# Pure_Sequencer.net
KiCad netlist of a schematic drawn in EAGLE
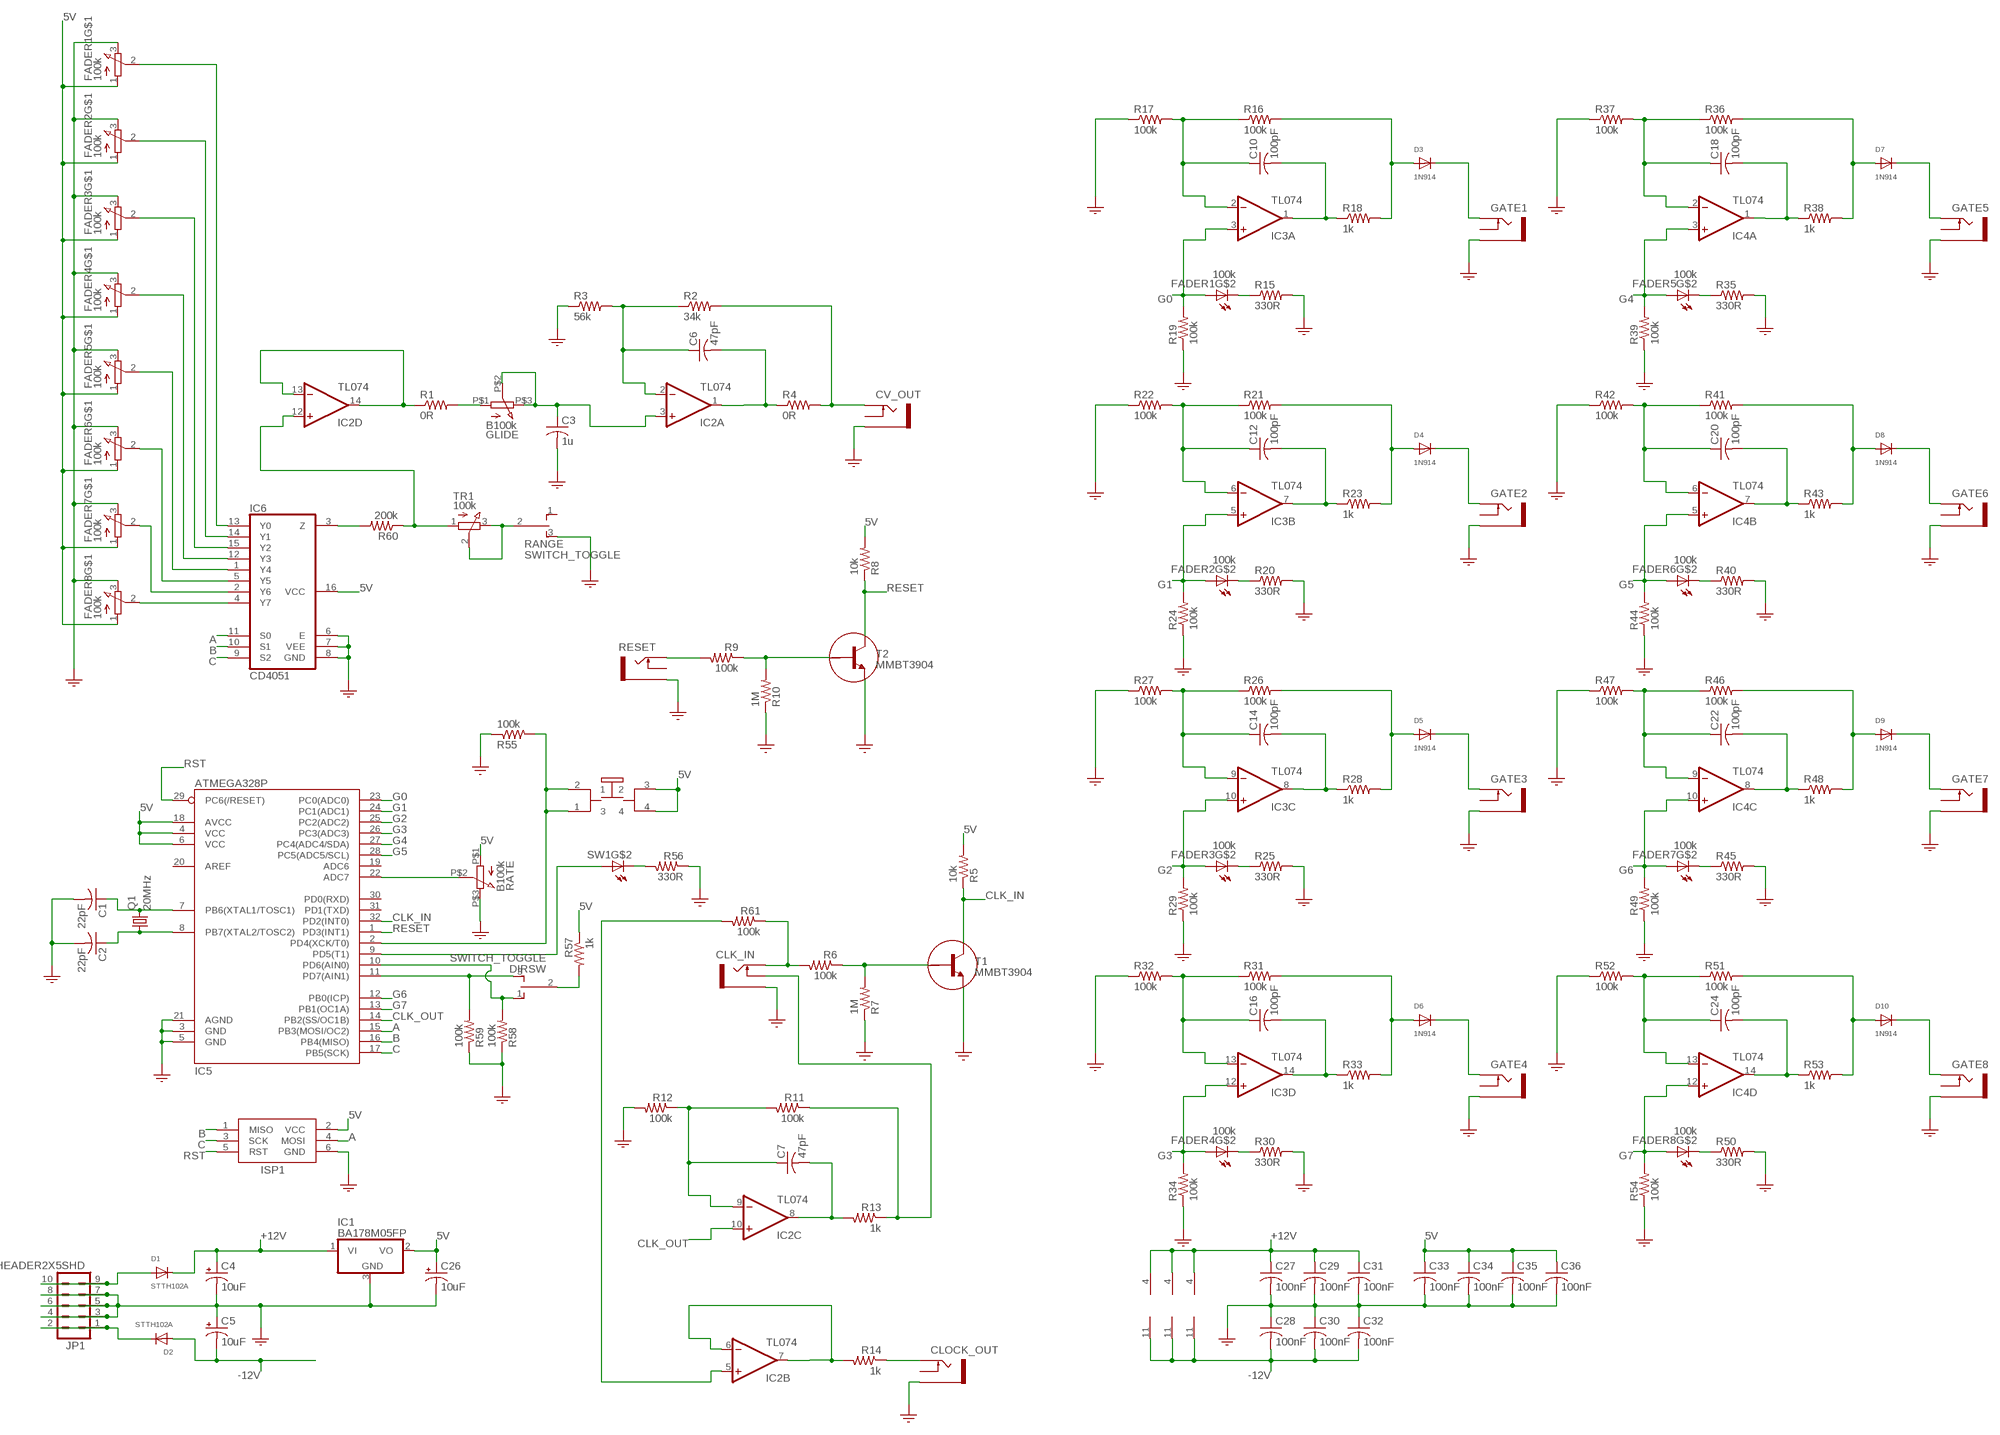
[diagram p0: schematic, sheet 1]

(export (version "E")
  (design (tool "Eeschema 10.0.6"))
  (components
    (comp (ref "C1")
      (value "22pF")
      (footprint "eagle-import:C0805")
      (libsource (lib "eagle-import") (part "CAPACITOR-USC0805"))
    )
    (comp (ref "C2")
      (value "22pF")
      (footprint "eagle-import:C0805")
      (libsource (lib "eagle-import") (part "CAPACITOR-USC0805"))
    )
    (comp (ref "C3")
      (value "1u")
      (footprint "eagle-import:C0805")
      (libsource (lib "eagle-import") (part "CAPACITOR-USC0805"))
    )
    (comp (ref "C4")
      (value "10uF")
      (footprint "eagle-import:153CLV-0505")
      (libsource (lib "eagle-import") (part "CAPACITOR_POL-US153CLV-0505"))
    )
    (comp (ref "C5")
      (value "10uF")
      (footprint "eagle-import:153CLV-0505")
      (libsource (lib "eagle-import") (part "CAPACITOR_POL-US153CLV-0505"))
    )
    (comp (ref "C6")
      (value "47pF")
      (footprint "eagle-import:C0805")
      (libsource (lib "eagle-import") (part "CAPACITOR-USC0805"))
    )
    (comp (ref "C7")
      (value "47pF")
      (footprint "eagle-import:C0805")
      (libsource (lib "eagle-import") (part "CAPACITOR-USC0805"))
    )
    (comp (ref "C10")
      (value "100pF")
      (footprint "eagle-import:C0805")
      (libsource (lib "eagle-import") (part "CAPACITOR-USC0805"))
    )
    (comp (ref "C12")
      (value "100pF")
      (footprint "eagle-import:C0805")
      (libsource (lib "eagle-import") (part "CAPACITOR-USC0805"))
    )
    (comp (ref "C14")
      (value "100pF")
      (footprint "eagle-import:C0805")
      (libsource (lib "eagle-import") (part "CAPACITOR-USC0805"))
    )
    (comp (ref "C16")
      (value "100pF")
      (footprint "eagle-import:C0805")
      (libsource (lib "eagle-import") (part "CAPACITOR-USC0805"))
    )
    (comp (ref "C18")
      (value "100pF")
      (footprint "eagle-import:C0805")
      (libsource (lib "eagle-import") (part "CAPACITOR-USC0805"))
    )
    (comp (ref "C20")
      (value "100pF")
      (footprint "eagle-import:C0805")
      (libsource (lib "eagle-import") (part "CAPACITOR-USC0805"))
    )
    (comp (ref "C22")
      (value "100pF")
      (footprint "eagle-import:C0805")
      (libsource (lib "eagle-import") (part "CAPACITOR-USC0805"))
    )
    (comp (ref "C24")
      (value "100pF")
      (footprint "eagle-import:C0805")
      (libsource (lib "eagle-import") (part "CAPACITOR-USC0805"))
    )
    (comp (ref "C26")
      (value "10uF")
      (footprint "eagle-import:153CLV-0505")
      (libsource (lib "eagle-import") (part "CAPACITOR_POL-US153CLV-0505"))
    )
    (comp (ref "C27")
      (value "100nF")
      (footprint "eagle-import:C0805")
      (libsource (lib "eagle-import") (part "CAPACITOR-USC0805"))
    )
    (comp (ref "C28")
      (value "100nF")
      (footprint "eagle-import:C0805")
      (libsource (lib "eagle-import") (part "CAPACITOR-USC0805"))
    )
    (comp (ref "C29")
      (value "100nF")
      (footprint "eagle-import:C0805")
      (libsource (lib "eagle-import") (part "CAPACITOR-USC0805"))
    )
    (comp (ref "C30")
      (value "100nF")
      (footprint "eagle-import:C0805")
      (libsource (lib "eagle-import") (part "CAPACITOR-USC0805"))
    )
    (comp (ref "C31")
      (value "100nF")
      (footprint "eagle-import:C0805")
      (libsource (lib "eagle-import") (part "CAPACITOR-USC0805"))
    )
    (comp (ref "C32")
      (value "100nF")
      (footprint "eagle-import:C0805")
      (libsource (lib "eagle-import") (part "CAPACITOR-USC0805"))
    )
    (comp (ref "C33")
      (value "100nF")
      (footprint "eagle-import:C0805")
      (libsource (lib "eagle-import") (part "CAPACITOR-USC0805"))
    )
    (comp (ref "C34")
      (value "100nF")
      (footprint "eagle-import:C0805")
      (libsource (lib "eagle-import") (part "CAPACITOR-USC0805"))
    )
    (comp (ref "C35")
      (value "100nF")
      (footprint "eagle-import:C0805")
      (libsource (lib "eagle-import") (part "CAPACITOR-USC0805"))
    )
    (comp (ref "C36")
      (value "100nF")
      (footprint "eagle-import:C0805")
      (libsource (lib "eagle-import") (part "CAPACITOR-USC0805"))
    )
    (comp (ref "CLK_IN")
      (value "PJ301M-12")
      (footprint "eagle-import:PJ301M-12")
      (libsource (lib "eagle-import") (part "SOCKET_MONO_3.5MMPJ301M-12"))
    )
    (comp (ref "CLOCK_OUT")
      (value "PJ301M-12")
      (footprint "eagle-import:PJ301M-12")
      (libsource (lib "eagle-import") (part "SOCKET_MONO_3.5MMPJ301M-12"))
    )
    (comp (ref "CV_OUT")
      (value "PJ301M-12")
      (footprint "eagle-import:PJ301M-12")
      (libsource (lib "eagle-import") (part "SOCKET_MONO_3.5MMPJ301M-12"))
    )
    (comp (ref "D1")
      (value "STTH102A")
      (footprint "eagle-import:SMADIODE")
      (libsource (lib "eagle-import") (part "DIODESMA"))
    )
    (comp (ref "D2")
      (value "STTH102A")
      (footprint "eagle-import:SMADIODE")
      (libsource (lib "eagle-import") (part "DIODESMA"))
    )
    (comp (ref "D3")
      (value "1N914")
      (footprint "eagle-import:DO-41")
      (libsource (lib "eagle-import") (part "DIODEDO-41"))
    )
    (comp (ref "D4")
      (value "1N914")
      (footprint "eagle-import:DO-41")
      (libsource (lib "eagle-import") (part "DIODEDO-41"))
    )
    (comp (ref "D5")
      (value "1N914")
      (footprint "eagle-import:DO-41")
      (libsource (lib "eagle-import") (part "DIODEDO-41"))
    )
    (comp (ref "D6")
      (value "1N914")
      (footprint "eagle-import:DO-41")
      (libsource (lib "eagle-import") (part "DIODEDO-41"))
    )
    (comp (ref "D7")
      (value "1N914")
      (footprint "eagle-import:DO-41")
      (libsource (lib "eagle-import") (part "DIODEDO-41"))
    )
    (comp (ref "D8")
      (value "1N914")
      (footprint "eagle-import:DO-41")
      (libsource (lib "eagle-import") (part "DIODEDO-41"))
    )
    (comp (ref "D9")
      (value "1N914")
      (footprint "eagle-import:DO-41")
      (libsource (lib "eagle-import") (part "DIODEDO-41"))
    )
    (comp (ref "D10")
      (value "1N914")
      (footprint "eagle-import:DO-41")
      (libsource (lib "eagle-import") (part "DIODEDO-41"))
    )
    (comp (ref "DIRSW")
      (value "SWITCH_TOGGLE")
      (footprint "eagle-import:TOGGLE_SW")
      (libsource (lib "eagle-import") (part "SWITCH_TOGGLE"))
    )
    (comp (ref "FADER1")
      (value "100k")
      (footprint "eagle-import:FADER_20MM_LED")
      (libsource (lib "eagle-import") (part "RESISTOR_VARIABLE_LED"))
    )
    (comp (ref "FADER2")
      (value "100k")
      (footprint "eagle-import:FADER_20MM_LED")
      (libsource (lib "eagle-import") (part "RESISTOR_VARIABLE_LED"))
    )
    (comp (ref "FADER3")
      (value "100k")
      (footprint "eagle-import:FADER_20MM_LED")
      (libsource (lib "eagle-import") (part "RESISTOR_VARIABLE_LED"))
    )
    (comp (ref "FADER4")
      (value "100k")
      (footprint "eagle-import:FADER_20MM_LED")
      (libsource (lib "eagle-import") (part "RESISTOR_VARIABLE_LED"))
    )
    (comp (ref "FADER5")
      (value "100k")
      (footprint "eagle-import:FADER_20MM_LED")
      (libsource (lib "eagle-import") (part "RESISTOR_VARIABLE_LED"))
    )
    (comp (ref "FADER6")
      (value "100k")
      (footprint "eagle-import:FADER_20MM_LED")
      (libsource (lib "eagle-import") (part "RESISTOR_VARIABLE_LED"))
    )
    (comp (ref "FADER7")
      (value "100k")
      (footprint "eagle-import:FADER_20MM_LED")
      (libsource (lib "eagle-import") (part "RESISTOR_VARIABLE_LED"))
    )
    (comp (ref "FADER8")
      (value "100k")
      (footprint "eagle-import:FADER_20MM_LED")
      (libsource (lib "eagle-import") (part "RESISTOR_VARIABLE_LED"))
    )
    (comp (ref "GATE1")
      (value "PJ301M-12")
      (footprint "eagle-import:PJ301M-12")
      (libsource (lib "eagle-import") (part "SOCKET_MONO_3.5MMPJ301M-12"))
    )
    (comp (ref "GATE2")
      (value "PJ301M-12")
      (footprint "eagle-import:PJ301M-12")
      (libsource (lib "eagle-import") (part "SOCKET_MONO_3.5MMPJ301M-12"))
    )
    (comp (ref "GATE3")
      (value "PJ301M-12")
      (footprint "eagle-import:PJ301M-12")
      (libsource (lib "eagle-import") (part "SOCKET_MONO_3.5MMPJ301M-12"))
    )
    (comp (ref "GATE4")
      (value "PJ301M-12")
      (footprint "eagle-import:PJ301M-12")
      (libsource (lib "eagle-import") (part "SOCKET_MONO_3.5MMPJ301M-12"))
    )
    (comp (ref "GATE5")
      (value "PJ301M-12")
      (footprint "eagle-import:PJ301M-12")
      (libsource (lib "eagle-import") (part "SOCKET_MONO_3.5MMPJ301M-12"))
    )
    (comp (ref "GATE6")
      (value "PJ301M-12")
      (footprint "eagle-import:PJ301M-12")
      (libsource (lib "eagle-import") (part "SOCKET_MONO_3.5MMPJ301M-12"))
    )
    (comp (ref "GATE7")
      (value "PJ301M-12")
      (footprint "eagle-import:PJ301M-12")
      (libsource (lib "eagle-import") (part "SOCKET_MONO_3.5MMPJ301M-12"))
    )
    (comp (ref "GATE8")
      (value "PJ301M-12")
      (footprint "eagle-import:PJ301M-12")
      (libsource (lib "eagle-import") (part "SOCKET_MONO_3.5MMPJ301M-12"))
    )
    (comp (ref "GLIDE")
      (value "B100k")
      (footprint "eagle-import:POTENTIOMETER_9MM")
      (libsource (lib "eagle-import") (part "RESISTOR_VARIABLE9MM_POT"))
    )
    (comp (ref "IC1")
      (value "BA178M05FP")
      (footprint "eagle-import:TO252")
      (libsource (lib "eagle-import") (part "VOLTAGE_REG_POSDT05"))
    )
    (comp (ref "IC2")
      (value "TL074")
      (footprint "eagle-import:SO14")
      (libsource (lib "eagle-import") (part "OPAMP_QUADD"))
    )
    (comp (ref "IC3")
      (value "TL074")
      (footprint "eagle-import:SO14")
      (libsource (lib "eagle-import") (part "OPAMP_QUADD"))
    )
    (comp (ref "IC4")
      (value "TL074")
      (footprint "eagle-import:SO14")
      (libsource (lib "eagle-import") (part "OPAMP_QUADD"))
    )
    (comp (ref "IC5")
      (value "ATMEGA328P")
      (footprint "eagle-import:TQFP32-08")
      (libsource (lib "eagle-import") (part "MICROPROCESSOR_ATMEGA328_SMT"))
    )
    (comp (ref "IC6")
      (value "CD4051")
      (footprint "eagle-import:SOIC_16")
      (libsource (lib "eagle-import") (part "MUX_1X8_CD4051"))
    )
    (comp (ref "ISP1")
      (value "HEADER2X3-6")
      (footprint "eagle-import:AVRISP")
      (libsource (lib "eagle-import") (part "HEADER2X3-6"))
    )
    (comp (ref "JP1")
      (value "HEADER2X5SHD")
      (footprint "eagle-import:2X5-SHROUDED")
      (libsource (lib "eagle-import") (part "HEADER2X5SHD"))
    )
    (comp (ref "Q1")
      (value "20MHz")
      (footprint "eagle-import:HC49UP")
      (libsource (lib "eagle-import") (part "CRYSTALHC49UP"))
    )
    (comp (ref "R1")
      (value "0R")
      (footprint "eagle-import:R0805")
      (libsource (lib "eagle-import") (part "RESISTOR_USR0805"))
    )
    (comp (ref "R2")
      (value "34k")
      (footprint "eagle-import:R0805")
      (libsource (lib "eagle-import") (part "RESISTOR_USR0805"))
    )
    (comp (ref "R3")
      (value "56k")
      (footprint "eagle-import:R0805")
      (libsource (lib "eagle-import") (part "RESISTOR_USR0805"))
    )
    (comp (ref "R4")
      (value "0R")
      (footprint "eagle-import:R0805")
      (libsource (lib "eagle-import") (part "RESISTOR_USR0805"))
    )
    (comp (ref "R5")
      (value "10k")
      (footprint "eagle-import:R0805")
      (libsource (lib "eagle-import") (part "RESISTOR_USR0805"))
    )
    (comp (ref "R6")
      (value "100k")
      (footprint "eagle-import:R0805")
      (libsource (lib "eagle-import") (part "RESISTOR_USR0805"))
    )
    (comp (ref "R7")
      (value "1M")
      (footprint "eagle-import:R0805")
      (libsource (lib "eagle-import") (part "RESISTOR_USR0805"))
    )
    (comp (ref "R8")
      (value "10k")
      (footprint "eagle-import:R0805")
      (libsource (lib "eagle-import") (part "RESISTOR_USR0805"))
    )
    (comp (ref "R9")
      (value "100k")
      (footprint "eagle-import:R0805")
      (libsource (lib "eagle-import") (part "RESISTOR_USR0805"))
    )
    (comp (ref "R10")
      (value "1M")
      (footprint "eagle-import:R0805")
      (libsource (lib "eagle-import") (part "RESISTOR_USR0805"))
    )
    (comp (ref "R11")
      (value "100k")
      (footprint "eagle-import:R0805")
      (libsource (lib "eagle-import") (part "RESISTOR_USR0805"))
    )
    (comp (ref "R12")
      (value "100k")
      (footprint "eagle-import:R0805")
      (libsource (lib "eagle-import") (part "RESISTOR_USR0805"))
    )
    (comp (ref "R13")
      (value "1k")
      (footprint "eagle-import:R0805")
      (libsource (lib "eagle-import") (part "RESISTOR_USR0805"))
    )
    (comp (ref "R14")
      (value "1k")
      (footprint "eagle-import:R0805")
      (libsource (lib "eagle-import") (part "RESISTOR_USR0805"))
    )
    (comp (ref "R15")
      (value "330R")
      (footprint "eagle-import:R0805")
      (libsource (lib "eagle-import") (part "RESISTOR_USR0805"))
    )
    (comp (ref "R16")
      (value "100k")
      (footprint "eagle-import:R0805")
      (libsource (lib "eagle-import") (part "RESISTOR_USR0805"))
    )
    (comp (ref "R17")
      (value "100k")
      (footprint "eagle-import:R0805")
      (libsource (lib "eagle-import") (part "RESISTOR_USR0805"))
    )
    (comp (ref "R18")
      (value "1k")
      (footprint "eagle-import:R0805")
      (libsource (lib "eagle-import") (part "RESISTOR_USR0805"))
    )
    (comp (ref "R19")
      (value "100k")
      (footprint "eagle-import:R0805")
      (libsource (lib "eagle-import") (part "RESISTOR_USR0805"))
    )
    (comp (ref "R20")
      (value "330R")
      (footprint "eagle-import:R0805")
      (libsource (lib "eagle-import") (part "RESISTOR_USR0805"))
    )
    (comp (ref "R21")
      (value "100k")
      (footprint "eagle-import:R0805")
      (libsource (lib "eagle-import") (part "RESISTOR_USR0805"))
    )
    (comp (ref "R22")
      (value "100k")
      (footprint "eagle-import:R0805")
      (libsource (lib "eagle-import") (part "RESISTOR_USR0805"))
    )
    (comp (ref "R23")
      (value "1k")
      (footprint "eagle-import:R0805")
      (libsource (lib "eagle-import") (part "RESISTOR_USR0805"))
    )
    (comp (ref "R24")
      (value "100k")
      (footprint "eagle-import:R0805")
      (libsource (lib "eagle-import") (part "RESISTOR_USR0805"))
    )
    (comp (ref "R25")
      (value "330R")
      (footprint "eagle-import:R0805")
      (libsource (lib "eagle-import") (part "RESISTOR_USR0805"))
    )
    (comp (ref "R26")
      (value "100k")
      (footprint "eagle-import:R0805")
      (libsource (lib "eagle-import") (part "RESISTOR_USR0805"))
    )
    (comp (ref "R27")
      (value "100k")
      (footprint "eagle-import:R0805")
      (libsource (lib "eagle-import") (part "RESISTOR_USR0805"))
    )
    (comp (ref "R28")
      (value "1k")
      (footprint "eagle-import:R0805")
      (libsource (lib "eagle-import") (part "RESISTOR_USR0805"))
    )
    (comp (ref "R29")
      (value "100k")
      (footprint "eagle-import:R0805")
      (libsource (lib "eagle-import") (part "RESISTOR_USR0805"))
    )
    (comp (ref "R30")
      (value "330R")
      (footprint "eagle-import:R0805")
      (libsource (lib "eagle-import") (part "RESISTOR_USR0805"))
    )
    (comp (ref "R31")
      (value "100k")
      (footprint "eagle-import:R0805")
      (libsource (lib "eagle-import") (part "RESISTOR_USR0805"))
    )
    (comp (ref "R32")
      (value "100k")
      (footprint "eagle-import:R0805")
      (libsource (lib "eagle-import") (part "RESISTOR_USR0805"))
    )
    (comp (ref "R33")
      (value "1k")
      (footprint "eagle-import:R0805")
      (libsource (lib "eagle-import") (part "RESISTOR_USR0805"))
    )
    (comp (ref "R34")
      (value "100k")
      (footprint "eagle-import:R0805")
      (libsource (lib "eagle-import") (part "RESISTOR_USR0805"))
    )
    (comp (ref "R35")
      (value "330R")
      (footprint "eagle-import:R0805")
      (libsource (lib "eagle-import") (part "RESISTOR_USR0805"))
    )
    (comp (ref "R36")
      (value "100k")
      (footprint "eagle-import:R0805")
      (libsource (lib "eagle-import") (part "RESISTOR_USR0805"))
    )
    (comp (ref "R37")
      (value "100k")
      (footprint "eagle-import:R0805")
      (libsource (lib "eagle-import") (part "RESISTOR_USR0805"))
    )
    (comp (ref "R38")
      (value "1k")
      (footprint "eagle-import:R0805")
      (libsource (lib "eagle-import") (part "RESISTOR_USR0805"))
    )
    (comp (ref "R39")
      (value "100k")
      (footprint "eagle-import:R0805")
      (libsource (lib "eagle-import") (part "RESISTOR_USR0805"))
    )
    (comp (ref "R40")
      (value "330R")
      (footprint "eagle-import:R0805")
      (libsource (lib "eagle-import") (part "RESISTOR_USR0805"))
    )
    (comp (ref "R41")
      (value "100k")
      (footprint "eagle-import:R0805")
      (libsource (lib "eagle-import") (part "RESISTOR_USR0805"))
    )
    (comp (ref "R42")
      (value "100k")
      (footprint "eagle-import:R0805")
      (libsource (lib "eagle-import") (part "RESISTOR_USR0805"))
    )
    (comp (ref "R43")
      (value "1k")
      (footprint "eagle-import:R0805")
      (libsource (lib "eagle-import") (part "RESISTOR_USR0805"))
    )
    (comp (ref "R44")
      (value "100k")
      (footprint "eagle-import:R0805")
      (libsource (lib "eagle-import") (part "RESISTOR_USR0805"))
    )
    (comp (ref "R45")
      (value "330R")
      (footprint "eagle-import:R0805")
      (libsource (lib "eagle-import") (part "RESISTOR_USR0805"))
    )
    (comp (ref "R46")
      (value "100k")
      (footprint "eagle-import:R0805")
      (libsource (lib "eagle-import") (part "RESISTOR_USR0805"))
    )
    (comp (ref "R47")
      (value "100k")
      (footprint "eagle-import:R0805")
      (libsource (lib "eagle-import") (part "RESISTOR_USR0805"))
    )
    (comp (ref "R48")
      (value "1k")
      (footprint "eagle-import:R0805")
      (libsource (lib "eagle-import") (part "RESISTOR_USR0805"))
    )
    (comp (ref "R49")
      (value "100k")
      (footprint "eagle-import:R0805")
      (libsource (lib "eagle-import") (part "RESISTOR_USR0805"))
    )
    (comp (ref "R50")
      (value "330R")
      (footprint "eagle-import:R0805")
      (libsource (lib "eagle-import") (part "RESISTOR_USR0805"))
    )
    (comp (ref "R51")
      (value "100k")
      (footprint "eagle-import:R0805")
      (libsource (lib "eagle-import") (part "RESISTOR_USR0805"))
    )
    (comp (ref "R52")
      (value "100k")
      (footprint "eagle-import:R0805")
      (libsource (lib "eagle-import") (part "RESISTOR_USR0805"))
    )
    (comp (ref "R53")
      (value "1k")
      (footprint "eagle-import:R0805")
      (libsource (lib "eagle-import") (part "RESISTOR_USR0805"))
    )
    (comp (ref "R54")
      (value "100k")
      (footprint "eagle-import:R0805")
      (libsource (lib "eagle-import") (part "RESISTOR_USR0805"))
    )
    (comp (ref "R55")
      (value "100k")
      (footprint "eagle-import:R0805")
      (libsource (lib "eagle-import") (part "RESISTOR_USR0805"))
    )
    (comp (ref "R56")
      (value "330R")
      (footprint "eagle-import:R0805")
      (libsource (lib "eagle-import") (part "RESISTOR_USR0805"))
    )
    (comp (ref "R57")
      (value "1k")
      (footprint "eagle-import:R0805")
      (libsource (lib "eagle-import") (part "RESISTOR_USR0805"))
    )
    (comp (ref "R58")
      (value "100k")
      (footprint "eagle-import:R0805")
      (libsource (lib "eagle-import") (part "RESISTOR_USR0805"))
    )
    (comp (ref "R59")
      (value "100k")
      (footprint "eagle-import:R0805")
      (libsource (lib "eagle-import") (part "RESISTOR_USR0805"))
    )
    (comp (ref "R60")
      (value "200k")
      (footprint "eagle-import:R0805")
      (libsource (lib "eagle-import") (part "RESISTOR_USR0805"))
    )
    (comp (ref "R61")
      (value "100k")
      (footprint "eagle-import:R0805")
      (libsource (lib "eagle-import") (part "RESISTOR_USR0805"))
    )
    (comp (ref "RANGE")
      (value "SWITCH_TOGGLE")
      (footprint "eagle-import:TOGGLE_SW")
      (libsource (lib "eagle-import") (part "SWITCH_TOGGLE"))
    )
    (comp (ref "RATE")
      (value "B100k")
      (footprint "eagle-import:POTENTIOMETER_9MM")
      (libsource (lib "eagle-import") (part "RESISTOR_VARIABLE9MM_POT"))
    )
    (comp (ref "RESET")
      (value "PJ301M-12")
      (footprint "eagle-import:PJ301M-12")
      (libsource (lib "eagle-import") (part "SOCKET_MONO_3.5MMPJ301M-12"))
    )
    (comp (ref "SW1")
      (value "SWITCH_PUSHBUTTON_LED")
      (footprint "eagle-import:PB6149L")
      (libsource (lib "eagle-import") (part "SWITCH_PUSHBUTTON_LED"))
    )
    (comp (ref "T1")
      (value "MMBT3904")
      (footprint "eagle-import:SOT23")
      (libsource (lib "eagle-import") (part "TRANSISTOR_NPNSOT23"))
    )
    (comp (ref "T2")
      (value "MMBT3904")
      (footprint "eagle-import:SOT23")
      (libsource (lib "eagle-import") (part "TRANSISTOR_NPNSOT23"))
    )
    (comp (ref "TR1")
      (value "100k")
      (footprint "eagle-import:TRIMMER_TH")
      (libsource (lib "eagle-import") (part "RESISTOR_VARIABLETRIMMER_TH"))
    )
  )
  (nets
    (net (code "1") (name "/+12V") (class "Default")
      (node (ref "C27") (pin "1") (pinfunction "1_1") (pintype "passive"))
      (node (ref "C29") (pin "1") (pinfunction "1_1") (pintype "passive"))
      (node (ref "C31") (pin "1") (pinfunction "1_1") (pintype "passive"))
      (node (ref "C4") (pin "+") (pinfunction "+_+") (pintype "passive"))
      (node (ref "D1") (pin "C") (pinfunction "C_C") (pintype "passive"))
      (node (ref "IC1") (pin "1") (pinfunction "VI_1") (pintype "input"))
      (node (ref "IC2") (pin "4") (pinfunction "V+_4") (pintype "power_in"))
      (node (ref "IC3") (pin "4") (pinfunction "V+_4") (pintype "power_in"))
      (node (ref "IC4") (pin "4") (pinfunction "V+_4") (pintype "power_in"))
    )
    (net (code "2") (name "/-12V") (class "Default")
      (node (ref "C28") (pin "2") (pinfunction "2_2") (pintype "passive"))
      (node (ref "C30") (pin "2") (pinfunction "2_2") (pintype "passive"))
      (node (ref "C32") (pin "2") (pinfunction "2_2") (pintype "passive"))
      (node (ref "C5") (pin "-") (pinfunction "-_-") (pintype "passive"))
      (node (ref "D2") (pin "A") (pinfunction "A_A") (pintype "passive"))
      (node (ref "IC2") (pin "11") (pinfunction "V-_11") (pintype "power_in"))
      (node (ref "IC3") (pin "11") (pinfunction "V-_11") (pintype "power_in"))
      (node (ref "IC4") (pin "11") (pinfunction "V-_11") (pintype "power_in"))
    )
    (net (code "3") (name "/5V") (class "Default")
      (node (ref "C26") (pin "+") (pinfunction "+_+") (pintype "passive"))
      (node (ref "C33") (pin "1") (pinfunction "1_1") (pintype "passive"))
      (node (ref "C34") (pin "1") (pinfunction "1_1") (pintype "passive"))
      (node (ref "C35") (pin "1") (pinfunction "1_1") (pintype "passive"))
      (node (ref "C36") (pin "1") (pinfunction "1_1") (pintype "passive"))
      (node (ref "FADER1") (pin "1") (pinfunction "1_1") (pintype "passive"))
      (node (ref "FADER2") (pin "1") (pinfunction "1_1") (pintype "passive"))
      (node (ref "FADER3") (pin "1") (pinfunction "1_1") (pintype "passive"))
      (node (ref "FADER4") (pin "1") (pinfunction "1_1") (pintype "passive"))
      (node (ref "FADER5") (pin "1") (pinfunction "1_1") (pintype "passive"))
      (node (ref "FADER6") (pin "1") (pinfunction "1_1") (pintype "passive"))
      (node (ref "FADER7") (pin "1") (pinfunction "1_1") (pintype "passive"))
      (node (ref "FADER8") (pin "1") (pinfunction "1_1") (pintype "passive"))
      (node (ref "IC1") (pin "2") (pinfunction "VO_2") (pintype "passive"))
      (node (ref "IC5") (pin "18") (pinfunction "AVCC_18") (pintype "bidirectional"))
      (node (ref "IC5") (pin "4") (pinfunction "VCC_4") (pintype "bidirectional"))
      (node (ref "IC5") (pin "6") (pinfunction "VCC_6") (pintype "bidirectional"))
      (node (ref "IC6") (pin "16") (pinfunction "VCC_16") (pintype "input"))
      (node (ref "ISP1") (pin "2") (pinfunction "VCC_2") (pintype "power_in"))
      (node (ref "R5") (pin "2") (pinfunction "2_2") (pintype "passive"))
      (node (ref "R57") (pin "1") (pinfunction "1_1") (pintype "passive"))
      (node (ref "R8") (pin "2") (pinfunction "2_2") (pintype "passive"))
      (node (ref "RATE") (pin "P$1") (pinfunction "1_P$1") (pintype "passive"))
      (node (ref "SW1") (pin "3") (pinfunction "2_3") (pintype "bidirectional"))
      (node (ref "SW1") (pin "4") (pinfunction "4_4") (pintype "bidirectional"))
    )
    (net (code "4") (name "/A") (class "Default")
      (node (ref "IC5") (pin "15") (pinfunction "PB3(MOSI/OC2)_15") (pintype "bidirectional"))
      (node (ref "IC6") (pin "11") (pinfunction "S0_11") (pintype "input"))
      (node (ref "ISP1") (pin "4") (pinfunction "MOSI_4") (pintype "output"))
    )
    (net (code "5") (name "/B") (class "Default")
      (node (ref "IC5") (pin "16") (pinfunction "PB4(MISO)_16") (pintype "bidirectional"))
      (node (ref "IC6") (pin "10") (pinfunction "S1_10") (pintype "input"))
      (node (ref "ISP1") (pin "1") (pinfunction "MISO_1") (pintype "input"))
    )
    (net (code "6") (name "/C") (class "Default")
      (node (ref "IC5") (pin "17") (pinfunction "PB5(SCK)_17") (pintype "bidirectional"))
      (node (ref "IC6") (pin "9") (pinfunction "S2_9") (pintype "input"))
      (node (ref "ISP1") (pin "3") (pinfunction "SCK_3") (pintype "output"))
    )
    (net (code "7") (name "/CLK_IN") (class "Default")
      (node (ref "IC5") (pin "32") (pinfunction "PD2(INT0)_32") (pintype "bidirectional"))
      (node (ref "R5") (pin "1") (pinfunction "1_1") (pintype "passive"))
      (node (ref "T1") (pin "3") (pinfunction "C_3") (pintype "passive"))
    )
    (net (code "8") (name "/CLK_OUT") (class "Default")
      (node (ref "IC2") (pin "10") (pinfunction "+IN_10") (pintype "input"))
      (node (ref "IC5") (pin "14") (pinfunction "PB2(SS/OC1B)_14") (pintype "bidirectional"))
    )
    (net (code "9") (name "/G0") (class "Default")
      (node (ref "FADER1") (pin "A") (pinfunction "A_A") (pintype "passive"))
      (node (ref "IC3") (pin "3") (pinfunction "+IN_3") (pintype "input"))
      (node (ref "IC5") (pin "23") (pinfunction "PC0(ADC0)_23") (pintype "bidirectional"))
      (node (ref "R19") (pin "2") (pinfunction "2_2") (pintype "passive"))
    )
    (net (code "10") (name "/G1") (class "Default")
      (node (ref "FADER2") (pin "A") (pinfunction "A_A") (pintype "passive"))
      (node (ref "IC3") (pin "5") (pinfunction "+IN_5") (pintype "input"))
      (node (ref "IC5") (pin "24") (pinfunction "PC1(ADC1)_24") (pintype "bidirectional"))
      (node (ref "R24") (pin "2") (pinfunction "2_2") (pintype "passive"))
    )
    (net (code "11") (name "/G2") (class "Default")
      (node (ref "FADER3") (pin "A") (pinfunction "A_A") (pintype "passive"))
      (node (ref "IC3") (pin "10") (pinfunction "+IN_10") (pintype "input"))
      (node (ref "IC5") (pin "25") (pinfunction "PC2(ADC2)_25") (pintype "bidirectional"))
      (node (ref "R29") (pin "2") (pinfunction "2_2") (pintype "passive"))
    )
    (net (code "12") (name "/G3") (class "Default")
      (node (ref "FADER4") (pin "A") (pinfunction "A_A") (pintype "passive"))
      (node (ref "IC3") (pin "12") (pinfunction "+IN_12") (pintype "input"))
      (node (ref "IC5") (pin "26") (pinfunction "PC3(ADC3)_26") (pintype "bidirectional"))
      (node (ref "R34") (pin "2") (pinfunction "2_2") (pintype "passive"))
    )
    (net (code "13") (name "/G4") (class "Default")
      (node (ref "FADER5") (pin "A") (pinfunction "A_A") (pintype "passive"))
      (node (ref "IC4") (pin "3") (pinfunction "+IN_3") (pintype "input"))
      (node (ref "IC5") (pin "27") (pinfunction "PC4(ADC4/SDA)_27") (pintype "bidirectional"))
      (node (ref "R39") (pin "2") (pinfunction "2_2") (pintype "passive"))
    )
    (net (code "14") (name "/G5") (class "Default")
      (node (ref "FADER6") (pin "A") (pinfunction "A_A") (pintype "passive"))
      (node (ref "IC4") (pin "5") (pinfunction "+IN_5") (pintype "input"))
      (node (ref "IC5") (pin "28") (pinfunction "PC5(ADC5/SCL)_28") (pintype "bidirectional"))
      (node (ref "R44") (pin "2") (pinfunction "2_2") (pintype "passive"))
    )
    (net (code "15") (name "/G6") (class "Default")
      (node (ref "FADER7") (pin "A") (pinfunction "A_A") (pintype "passive"))
      (node (ref "IC4") (pin "10") (pinfunction "+IN_10") (pintype "input"))
      (node (ref "IC5") (pin "12") (pinfunction "PB0(ICP)_12") (pintype "bidirectional"))
      (node (ref "R49") (pin "2") (pinfunction "2_2") (pintype "passive"))
    )
    (net (code "16") (name "/G7") (class "Default")
      (node (ref "FADER8") (pin "A") (pinfunction "A_A") (pintype "passive"))
      (node (ref "IC4") (pin "12") (pinfunction "+IN_12") (pintype "input"))
      (node (ref "IC5") (pin "13") (pinfunction "PB1(OC1A)_13") (pintype "bidirectional"))
      (node (ref "R54") (pin "2") (pinfunction "2_2") (pintype "passive"))
    )
    (net (code "17") (name "/RESET") (class "Default")
      (node (ref "IC5") (pin "1") (pinfunction "PD3(INT1)_1") (pintype "bidirectional"))
      (node (ref "R8") (pin "1") (pinfunction "1_1") (pintype "passive"))
      (node (ref "T2") (pin "3") (pinfunction "C_3") (pintype "passive"))
    )
    (net (code "18") (name "/RST") (class "Default")
      (node (ref "IC5") (pin "29") (pinfunction "PC6(/RESET)_29") (pintype "bidirectional"))
      (node (ref "ISP1") (pin "5") (pinfunction "RST_5") (pintype "output"))
    )
    (net (code "19") (name "GND") (class "Default")
      (node (ref "C1") (pin "2") (pinfunction "2_2") (pintype "passive"))
      (node (ref "C2") (pin "2") (pinfunction "2_2") (pintype "passive"))
      (node (ref "C26") (pin "-") (pinfunction "-_-") (pintype "passive"))
      (node (ref "C27") (pin "2") (pinfunction "2_2") (pintype "passive"))
      (node (ref "C28") (pin "1") (pinfunction "1_1") (pintype "passive"))
      (node (ref "C29") (pin "2") (pinfunction "2_2") (pintype "passive"))
      (node (ref "C3") (pin "2") (pinfunction "2_2") (pintype "passive"))
      (node (ref "C30") (pin "1") (pinfunction "1_1") (pintype "passive"))
      (node (ref "C31") (pin "2") (pinfunction "2_2") (pintype "passive"))
      (node (ref "C32") (pin "1") (pinfunction "1_1") (pintype "passive"))
      (node (ref "C33") (pin "2") (pinfunction "2_2") (pintype "passive"))
      (node (ref "C34") (pin "2") (pinfunction "2_2") (pintype "passive"))
      (node (ref "C35") (pin "2") (pinfunction "2_2") (pintype "passive"))
      (node (ref "C36") (pin "2") (pinfunction "2_2") (pintype "passive"))
      (node (ref "C4") (pin "-") (pinfunction "-_-") (pintype "passive"))
      (node (ref "C5") (pin "+") (pinfunction "+_+") (pintype "passive"))
      (node (ref "CLK_IN") (pin "GND") (pinfunction "SLEEVE_GND") (pintype "passive"))
      (node (ref "CLOCK_OUT") (pin "GND") (pinfunction "SLEEVE_GND") (pintype "passive"))
      (node (ref "CV_OUT") (pin "GND") (pinfunction "SLEEVE_GND") (pintype "passive"))
      (node (ref "FADER1") (pin "3") (pinfunction "3_3") (pintype "passive"))
      (node (ref "FADER2") (pin "3") (pinfunction "3_3") (pintype "passive"))
      (node (ref "FADER3") (pin "3") (pinfunction "3_3") (pintype "passive"))
      (node (ref "FADER4") (pin "3") (pinfunction "3_3") (pintype "passive"))
      (node (ref "FADER5") (pin "3") (pinfunction "3_3") (pintype "passive"))
      (node (ref "FADER6") (pin "3") (pinfunction "3_3") (pintype "passive"))
      (node (ref "FADER7") (pin "3") (pinfunction "3_3") (pintype "passive"))
      (node (ref "FADER8") (pin "3") (pinfunction "3_3") (pintype "passive"))
      (node (ref "GATE1") (pin "GND") (pinfunction "SLEEVE_GND") (pintype "passive"))
      (node (ref "GATE2") (pin "GND") (pinfunction "SLEEVE_GND") (pintype "passive"))
      (node (ref "GATE3") (pin "GND") (pinfunction "SLEEVE_GND") (pintype "passive"))
      (node (ref "GATE4") (pin "GND") (pinfunction "SLEEVE_GND") (pintype "passive"))
      (node (ref "GATE5") (pin "GND") (pinfunction "SLEEVE_GND") (pintype "passive"))
      (node (ref "GATE6") (pin "GND") (pinfunction "SLEEVE_GND") (pintype "passive"))
      (node (ref "GATE7") (pin "GND") (pinfunction "SLEEVE_GND") (pintype "passive"))
      (node (ref "GATE8") (pin "GND") (pinfunction "SLEEVE_GND") (pintype "passive"))
      (node (ref "IC1") (pin "3") (pinfunction "GND_3") (pintype "passive"))
      (node (ref "IC5") (pin "21") (pinfunction "AGND_21") (pintype "bidirectional"))
      (node (ref "IC5") (pin "3") (pinfunction "GND_3") (pintype "bidirectional"))
      (node (ref "IC5") (pin "5") (pinfunction "GND_5") (pintype "bidirectional"))
      (node (ref "IC6") (pin "6") (pinfunction "E_6") (pintype "bidirectional"))
      (node (ref "IC6") (pin "7") (pinfunction "VEE_7") (pintype "bidirectional"))
      (node (ref "IC6") (pin "8") (pinfunction "GND_8") (pintype "bidirectional"))
      (node (ref "ISP1") (pin "6") (pinfunction "GND_6") (pintype "power_in"))
      (node (ref "JP1") (pin "3") (pinfunction "3_3") (pintype "passive"))
      (node (ref "JP1") (pin "4") (pinfunction "4_4") (pintype "passive"))
      (node (ref "JP1") (pin "5") (pinfunction "5_5") (pintype "passive"))
      (node (ref "JP1") (pin "6") (pinfunction "6_6") (pintype "passive"))
      (node (ref "JP1") (pin "7") (pinfunction "7_7") (pintype "passive"))
      (node (ref "JP1") (pin "8") (pinfunction "8_8") (pintype "passive"))
      (node (ref "R10") (pin "1") (pinfunction "1_1") (pintype "passive"))
      (node (ref "R12") (pin "2") (pinfunction "2_2") (pintype "passive"))
      (node (ref "R15") (pin "2") (pinfunction "2_2") (pintype "passive"))
      (node (ref "R17") (pin "1") (pinfunction "1_1") (pintype "passive"))
      (node (ref "R19") (pin "1") (pinfunction "1_1") (pintype "passive"))
      (node (ref "R20") (pin "2") (pinfunction "2_2") (pintype "passive"))
      (node (ref "R22") (pin "1") (pinfunction "1_1") (pintype "passive"))
      (node (ref "R24") (pin "1") (pinfunction "1_1") (pintype "passive"))
      (node (ref "R25") (pin "2") (pinfunction "2_2") (pintype "passive"))
      (node (ref "R27") (pin "1") (pinfunction "1_1") (pintype "passive"))
      (node (ref "R29") (pin "1") (pinfunction "1_1") (pintype "passive"))
      (node (ref "R3") (pin "1") (pinfunction "1_1") (pintype "passive"))
      (node (ref "R30") (pin "2") (pinfunction "2_2") (pintype "passive"))
      (node (ref "R32") (pin "1") (pinfunction "1_1") (pintype "passive"))
      (node (ref "R34") (pin "1") (pinfunction "1_1") (pintype "passive"))
      (node (ref "R35") (pin "2") (pinfunction "2_2") (pintype "passive"))
      (node (ref "R37") (pin "1") (pinfunction "1_1") (pintype "passive"))
      (node (ref "R39") (pin "1") (pinfunction "1_1") (pintype "passive"))
      (node (ref "R40") (pin "2") (pinfunction "2_2") (pintype "passive"))
      (node (ref "R42") (pin "1") (pinfunction "1_1") (pintype "passive"))
      (node (ref "R44") (pin "1") (pinfunction "1_1") (pintype "passive"))
      (node (ref "R45") (pin "2") (pinfunction "2_2") (pintype "passive"))
      (node (ref "R47") (pin "1") (pinfunction "1_1") (pintype "passive"))
      (node (ref "R49") (pin "1") (pinfunction "1_1") (pintype "passive"))
      (node (ref "R50") (pin "2") (pinfunction "2_2") (pintype "passive"))
      (node (ref "R52") (pin "1") (pinfunction "1_1") (pintype "passive"))
      (node (ref "R54") (pin "1") (pinfunction "1_1") (pintype "passive"))
      (node (ref "R55") (pin "1") (pinfunction "1_1") (pintype "passive"))
      (node (ref "R56") (pin "1") (pinfunction "1_1") (pintype "passive"))
      (node (ref "R58") (pin "1") (pinfunction "1_1") (pintype "passive"))
      (node (ref "R59") (pin "1") (pinfunction "1_1") (pintype "passive"))
      (node (ref "R7") (pin "1") (pinfunction "1_1") (pintype "passive"))
      (node (ref "RANGE") (pin "3") (pinfunction "S_3") (pintype "passive"))
      (node (ref "RATE") (pin "P$3") (pinfunction "3_P$3") (pintype "passive"))
      (node (ref "RESET") (pin "GND") (pinfunction "SLEEVE_GND") (pintype "passive"))
      (node (ref "T1") (pin "2") (pinfunction "E_2") (pintype "passive"))
      (node (ref "T2") (pin "2") (pinfunction "E_2") (pintype "passive"))
    )
    (net (code "20") (name "Net-(CLK_IN-PadTIP)") (class "Default")
      (node (ref "CLK_IN") (pin "TIP") (pinfunction "TIP_TIP") (pintype "passive"))
      (node (ref "R6") (pin "2") (pinfunction "2_2") (pintype "passive"))
      (node (ref "R61") (pin "1") (pinfunction "1_1") (pintype "passive"))
    )
    (net (code "21") (name "Net-(CLK_IN-SWITCH)") (class "Default")
      (node (ref "CLK_IN") (pin "NORM") (pinfunction "SWITCH_NORM") (pintype "passive"))
      (node (ref "R11") (pin "1") (pinfunction "1_1") (pintype "passive"))
      (node (ref "R13") (pin "1") (pinfunction "1_1") (pintype "passive"))
    )
    (net (code "22") (name "Net-(CLOCK_OUT-PadTIP)") (class "Default")
      (node (ref "CLOCK_OUT") (pin "TIP") (pinfunction "TIP_TIP") (pintype "passive"))
      (node (ref "R14") (pin "1") (pinfunction "1_1") (pintype "passive"))
    )
    (net (code "23") (name "Net-(CV_OUT-PadTIP)") (class "Default")
      (node (ref "CV_OUT") (pin "TIP") (pinfunction "TIP_TIP") (pintype "passive"))
      (node (ref "R2") (pin "2") (pinfunction "2_2") (pintype "passive"))
      (node (ref "R4") (pin "2") (pinfunction "2_2") (pintype "passive"))
    )
    (net (code "24") (name "Net-(D1-PadA)") (class "Default")
      (node (ref "D1") (pin "A") (pinfunction "A_A") (pintype "passive"))
      (node (ref "JP1") (pin "10") (pinfunction "10_10") (pintype "passive"))
      (node (ref "JP1") (pin "9") (pinfunction "9_9") (pintype "passive"))
    )
    (net (code "25") (name "Net-(D2-PadC)") (class "Default")
      (node (ref "D2") (pin "C") (pinfunction "C_C") (pintype "passive"))
      (node (ref "JP1") (pin "1") (pinfunction "1_1") (pintype "passive"))
      (node (ref "JP1") (pin "2") (pinfunction "2_2") (pintype "passive"))
    )
    (net (code "26") (name "Net-(D3-PadA)") (class "Default")
      (node (ref "D3") (pin "A") (pinfunction "A_A") (pintype "passive"))
      (node (ref "R16") (pin "2") (pinfunction "2_2") (pintype "passive"))
      (node (ref "R18") (pin "2") (pinfunction "2_2") (pintype "passive"))
    )
    (net (code "27") (name "Net-(D3-PadC)") (class "Default")
      (node (ref "D3") (pin "C") (pinfunction "C_C") (pintype "passive"))
      (node (ref "GATE1") (pin "TIP") (pinfunction "TIP_TIP") (pintype "passive"))
    )
    (net (code "28") (name "Net-(D4-PadA)") (class "Default")
      (node (ref "D4") (pin "A") (pinfunction "A_A") (pintype "passive"))
      (node (ref "R21") (pin "2") (pinfunction "2_2") (pintype "passive"))
      (node (ref "R23") (pin "2") (pinfunction "2_2") (pintype "passive"))
    )
    (net (code "29") (name "Net-(D4-PadC)") (class "Default")
      (node (ref "D4") (pin "C") (pinfunction "C_C") (pintype "passive"))
      (node (ref "GATE2") (pin "TIP") (pinfunction "TIP_TIP") (pintype "passive"))
    )
    (net (code "30") (name "Net-(D5-PadA)") (class "Default")
      (node (ref "D5") (pin "A") (pinfunction "A_A") (pintype "passive"))
      (node (ref "R26") (pin "2") (pinfunction "2_2") (pintype "passive"))
      (node (ref "R28") (pin "2") (pinfunction "2_2") (pintype "passive"))
    )
    (net (code "31") (name "Net-(D5-PadC)") (class "Default")
      (node (ref "D5") (pin "C") (pinfunction "C_C") (pintype "passive"))
      (node (ref "GATE3") (pin "TIP") (pinfunction "TIP_TIP") (pintype "passive"))
    )
    (net (code "32") (name "Net-(D6-PadA)") (class "Default")
      (node (ref "D6") (pin "A") (pinfunction "A_A") (pintype "passive"))
      (node (ref "R31") (pin "2") (pinfunction "2_2") (pintype "passive"))
      (node (ref "R33") (pin "2") (pinfunction "2_2") (pintype "passive"))
    )
    (net (code "33") (name "Net-(D6-PadC)") (class "Default")
      (node (ref "D6") (pin "C") (pinfunction "C_C") (pintype "passive"))
      (node (ref "GATE4") (pin "TIP") (pinfunction "TIP_TIP") (pintype "passive"))
    )
    (net (code "34") (name "Net-(D7-PadA)") (class "Default")
      (node (ref "D7") (pin "A") (pinfunction "A_A") (pintype "passive"))
      (node (ref "R36") (pin "2") (pinfunction "2_2") (pintype "passive"))
      (node (ref "R38") (pin "2") (pinfunction "2_2") (pintype "passive"))
    )
    (net (code "35") (name "Net-(D7-PadC)") (class "Default")
      (node (ref "D7") (pin "C") (pinfunction "C_C") (pintype "passive"))
      (node (ref "GATE5") (pin "TIP") (pinfunction "TIP_TIP") (pintype "passive"))
    )
    (net (code "36") (name "Net-(D8-PadA)") (class "Default")
      (node (ref "D8") (pin "A") (pinfunction "A_A") (pintype "passive"))
      (node (ref "R41") (pin "2") (pinfunction "2_2") (pintype "passive"))
      (node (ref "R43") (pin "2") (pinfunction "2_2") (pintype "passive"))
    )
    (net (code "37") (name "Net-(D8-PadC)") (class "Default")
      (node (ref "D8") (pin "C") (pinfunction "C_C") (pintype "passive"))
      (node (ref "GATE6") (pin "TIP") (pinfunction "TIP_TIP") (pintype "passive"))
    )
    (net (code "38") (name "Net-(D9-PadA)") (class "Default")
      (node (ref "D9") (pin "A") (pinfunction "A_A") (pintype "passive"))
      (node (ref "R46") (pin "2") (pinfunction "2_2") (pintype "passive"))
      (node (ref "R48") (pin "2") (pinfunction "2_2") (pintype "passive"))
    )
    (net (code "39") (name "Net-(D9-PadC)") (class "Default")
      (node (ref "D9") (pin "C") (pinfunction "C_C") (pintype "passive"))
      (node (ref "GATE7") (pin "TIP") (pinfunction "TIP_TIP") (pintype "passive"))
    )
    (net (code "40") (name "Net-(D10-PadA)") (class "Default")
      (node (ref "D10") (pin "A") (pinfunction "A_A") (pintype "passive"))
      (node (ref "R51") (pin "2") (pinfunction "2_2") (pintype "passive"))
      (node (ref "R53") (pin "2") (pinfunction "2_2") (pintype "passive"))
    )
    (net (code "41") (name "Net-(D10-PadC)") (class "Default")
      (node (ref "D10") (pin "C") (pinfunction "C_C") (pintype "passive"))
      (node (ref "GATE8") (pin "TIP") (pinfunction "TIP_TIP") (pintype "passive"))
    )
    (net (code "42") (name "Net-(DIRSW-O)") (class "Default")
      (node (ref "DIRSW") (pin "1") (pinfunction "O_1") (pintype "passive"))
      (node (ref "IC5") (pin "10") (pinfunction "PD6(AIN0)_10") (pintype "bidirectional"))
      (node (ref "R58") (pin "2") (pinfunction "2_2") (pintype "passive"))
    )
    (net (code "43") (name "Net-(DIRSW-P)") (class "Default")
      (node (ref "DIRSW") (pin "2") (pinfunction "P_2") (pintype "passive"))
      (node (ref "R57") (pin "2") (pinfunction "2_2") (pintype "passive"))
    )
    (net (code "44") (name "Net-(DIRSW-S)") (class "Default")
      (node (ref "DIRSW") (pin "3") (pinfunction "S_3") (pintype "passive"))
      (node (ref "IC5") (pin "11") (pinfunction "PD7(AIN1)_11") (pintype "bidirectional"))
      (node (ref "R59") (pin "2") (pinfunction "2_2") (pintype "passive"))
    )
    (net (code "45") (name "Net-(FADER1B-C)") (class "Default")
      (node (ref "FADER1") (pin "K") (pinfunction "C_K") (pintype "passive"))
      (node (ref "R15") (pin "1") (pinfunction "1_1") (pintype "passive"))
    )
    (net (code "46") (name "Net-(FADER2B-C)") (class "Default")
      (node (ref "FADER2") (pin "K") (pinfunction "C_K") (pintype "passive"))
      (node (ref "R20") (pin "1") (pinfunction "1_1") (pintype "passive"))
    )
    (net (code "47") (name "Net-(FADER3B-C)") (class "Default")
      (node (ref "FADER3") (pin "K") (pinfunction "C_K") (pintype "passive"))
      (node (ref "R25") (pin "1") (pinfunction "1_1") (pintype "passive"))
    )
    (net (code "48") (name "Net-(FADER4B-C)") (class "Default")
      (node (ref "FADER4") (pin "K") (pinfunction "C_K") (pintype "passive"))
      (node (ref "R30") (pin "1") (pinfunction "1_1") (pintype "passive"))
    )
    (net (code "49") (name "Net-(FADER5B-C)") (class "Default")
      (node (ref "FADER5") (pin "K") (pinfunction "C_K") (pintype "passive"))
      (node (ref "R35") (pin "1") (pinfunction "1_1") (pintype "passive"))
    )
    (net (code "50") (name "Net-(FADER6B-C)") (class "Default")
      (node (ref "FADER6") (pin "K") (pinfunction "C_K") (pintype "passive"))
      (node (ref "R40") (pin "1") (pinfunction "1_1") (pintype "passive"))
    )
    (net (code "51") (name "Net-(FADER7B-C)") (class "Default")
      (node (ref "FADER7") (pin "K") (pinfunction "C_K") (pintype "passive"))
      (node (ref "R45") (pin "1") (pinfunction "1_1") (pintype "passive"))
    )
    (net (code "52") (name "Net-(FADER8B-C)") (class "Default")
      (node (ref "FADER8") (pin "K") (pinfunction "C_K") (pintype "passive"))
      (node (ref "R50") (pin "1") (pinfunction "1_1") (pintype "passive"))
    )
    (net (code "53") (name "Net-(GLIDE-1)") (class "Default")
      (node (ref "GLIDE") (pin "P$1") (pinfunction "1_P$1") (pintype "passive"))
      (node (ref "R1") (pin "2") (pinfunction "2_2") (pintype "passive"))
    )
    (net (code "54") (name "Net-(GLIDE-2)") (class "Default")
      (node (ref "C3") (pin "1") (pinfunction "1_1") (pintype "passive"))
      (node (ref "GLIDE") (pin "P$2") (pinfunction "2_P$2") (pintype "passive"))
      (node (ref "GLIDE") (pin "P$3") (pinfunction "3_P$3") (pintype "passive"))
      (node (ref "IC2") (pin "3") (pinfunction "+IN_3") (pintype "input"))
    )
    (net (code "55") (name "Net-(IC2A--IN)") (class "Default")
      (node (ref "C6") (pin "1") (pinfunction "1_1") (pintype "passive"))
      (node (ref "IC2") (pin "2") (pinfunction "-IN_2") (pintype "input"))
      (node (ref "R2") (pin "1") (pinfunction "1_1") (pintype "passive"))
      (node (ref "R3") (pin "2") (pinfunction "2_2") (pintype "passive"))
    )
    (net (code "56") (name "Net-(IC2A-OUT)") (class "Default")
      (node (ref "C6") (pin "2") (pinfunction "2_2") (pintype "passive"))
      (node (ref "IC2") (pin "1") (pinfunction "OUT_1") (pintype "output"))
      (node (ref "R4") (pin "1") (pinfunction "1_1") (pintype "passive"))
    )
    (net (code "57") (name "Net-(IC2B-+IN)") (class "Default")
      (node (ref "IC2") (pin "5") (pinfunction "+IN_5") (pintype "input"))
      (node (ref "R61") (pin "2") (pinfunction "2_2") (pintype "passive"))
    )
    (net (code "58") (name "Net-(IC2B--IN)") (class "Default")
      (node (ref "IC2") (pin "6") (pinfunction "-IN_6") (pintype "input"))
      (node (ref "IC2") (pin "7") (pinfunction "OUT_7") (pintype "output"))
      (node (ref "R14") (pin "2") (pinfunction "2_2") (pintype "passive"))
    )
    (net (code "59") (name "Net-(IC2C--IN)") (class "Default")
      (node (ref "C7") (pin "1") (pinfunction "1_1") (pintype "passive"))
      (node (ref "IC2") (pin "9") (pinfunction "-IN_9") (pintype "input"))
      (node (ref "R11") (pin "2") (pinfunction "2_2") (pintype "passive"))
      (node (ref "R12") (pin "1") (pinfunction "1_1") (pintype "passive"))
    )
    (net (code "60") (name "Net-(IC2C-OUT)") (class "Default")
      (node (ref "C7") (pin "2") (pinfunction "2_2") (pintype "passive"))
      (node (ref "IC2") (pin "8") (pinfunction "OUT_8") (pintype "output"))
      (node (ref "R13") (pin "2") (pinfunction "2_2") (pintype "passive"))
    )
    (net (code "61") (name "Net-(IC2D-+IN)") (class "Default")
      (node (ref "IC2") (pin "12") (pinfunction "+IN_12") (pintype "input"))
      (node (ref "R60") (pin "1") (pinfunction "1_1") (pintype "passive"))
      (node (ref "TR1") (pin "1") (pinfunction "1_1") (pintype "passive"))
    )
    (net (code "62") (name "Net-(IC2D--IN)") (class "Default")
      (node (ref "IC2") (pin "13") (pinfunction "-IN_13") (pintype "input"))
      (node (ref "IC2") (pin "14") (pinfunction "OUT_14") (pintype "output"))
      (node (ref "R1") (pin "1") (pinfunction "1_1") (pintype "passive"))
    )
    (net (code "63") (name "Net-(IC3A--IN)") (class "Default")
      (node (ref "C10") (pin "1") (pinfunction "1_1") (pintype "passive"))
      (node (ref "IC3") (pin "2") (pinfunction "-IN_2") (pintype "input"))
      (node (ref "R16") (pin "1") (pinfunction "1_1") (pintype "passive"))
      (node (ref "R17") (pin "2") (pinfunction "2_2") (pintype "passive"))
    )
    (net (code "64") (name "Net-(IC3A-OUT)") (class "Default")
      (node (ref "C10") (pin "2") (pinfunction "2_2") (pintype "passive"))
      (node (ref "IC3") (pin "1") (pinfunction "OUT_1") (pintype "output"))
      (node (ref "R18") (pin "1") (pinfunction "1_1") (pintype "passive"))
    )
    (net (code "65") (name "Net-(IC3B--IN)") (class "Default")
      (node (ref "C12") (pin "1") (pinfunction "1_1") (pintype "passive"))
      (node (ref "IC3") (pin "6") (pinfunction "-IN_6") (pintype "input"))
      (node (ref "R21") (pin "1") (pinfunction "1_1") (pintype "passive"))
      (node (ref "R22") (pin "2") (pinfunction "2_2") (pintype "passive"))
    )
    (net (code "66") (name "Net-(IC3B-OUT)") (class "Default")
      (node (ref "C12") (pin "2") (pinfunction "2_2") (pintype "passive"))
      (node (ref "IC3") (pin "7") (pinfunction "OUT_7") (pintype "output"))
      (node (ref "R23") (pin "1") (pinfunction "1_1") (pintype "passive"))
    )
    (net (code "67") (name "Net-(IC3C--IN)") (class "Default")
      (node (ref "C14") (pin "1") (pinfunction "1_1") (pintype "passive"))
      (node (ref "IC3") (pin "9") (pinfunction "-IN_9") (pintype "input"))
      (node (ref "R26") (pin "1") (pinfunction "1_1") (pintype "passive"))
      (node (ref "R27") (pin "2") (pinfunction "2_2") (pintype "passive"))
    )
    (net (code "68") (name "Net-(IC3C-OUT)") (class "Default")
      (node (ref "C14") (pin "2") (pinfunction "2_2") (pintype "passive"))
      (node (ref "IC3") (pin "8") (pinfunction "OUT_8") (pintype "output"))
      (node (ref "R28") (pin "1") (pinfunction "1_1") (pintype "passive"))
    )
    (net (code "69") (name "Net-(IC3D--IN)") (class "Default")
      (node (ref "C16") (pin "1") (pinfunction "1_1") (pintype "passive"))
      (node (ref "IC3") (pin "13") (pinfunction "-IN_13") (pintype "input"))
      (node (ref "R31") (pin "1") (pinfunction "1_1") (pintype "passive"))
      (node (ref "R32") (pin "2") (pinfunction "2_2") (pintype "passive"))
    )
    (net (code "70") (name "Net-(IC3D-OUT)") (class "Default")
      (node (ref "C16") (pin "2") (pinfunction "2_2") (pintype "passive"))
      (node (ref "IC3") (pin "14") (pinfunction "OUT_14") (pintype "output"))
      (node (ref "R33") (pin "1") (pinfunction "1_1") (pintype "passive"))
    )
    (net (code "71") (name "Net-(IC4A--IN)") (class "Default")
      (node (ref "C18") (pin "1") (pinfunction "1_1") (pintype "passive"))
      (node (ref "IC4") (pin "2") (pinfunction "-IN_2") (pintype "input"))
      (node (ref "R36") (pin "1") (pinfunction "1_1") (pintype "passive"))
      (node (ref "R37") (pin "2") (pinfunction "2_2") (pintype "passive"))
    )
    (net (code "72") (name "Net-(IC4A-OUT)") (class "Default")
      (node (ref "C18") (pin "2") (pinfunction "2_2") (pintype "passive"))
      (node (ref "IC4") (pin "1") (pinfunction "OUT_1") (pintype "output"))
      (node (ref "R38") (pin "1") (pinfunction "1_1") (pintype "passive"))
    )
    (net (code "73") (name "Net-(IC4B--IN)") (class "Default")
      (node (ref "C20") (pin "1") (pinfunction "1_1") (pintype "passive"))
      (node (ref "IC4") (pin "6") (pinfunction "-IN_6") (pintype "input"))
      (node (ref "R41") (pin "1") (pinfunction "1_1") (pintype "passive"))
      (node (ref "R42") (pin "2") (pinfunction "2_2") (pintype "passive"))
    )
    (net (code "74") (name "Net-(IC4B-OUT)") (class "Default")
      (node (ref "C20") (pin "2") (pinfunction "2_2") (pintype "passive"))
      (node (ref "IC4") (pin "7") (pinfunction "OUT_7") (pintype "output"))
      (node (ref "R43") (pin "1") (pinfunction "1_1") (pintype "passive"))
    )
    (net (code "75") (name "Net-(IC4C--IN)") (class "Default")
      (node (ref "C22") (pin "1") (pinfunction "1_1") (pintype "passive"))
      (node (ref "IC4") (pin "9") (pinfunction "-IN_9") (pintype "input"))
      (node (ref "R46") (pin "1") (pinfunction "1_1") (pintype "passive"))
      (node (ref "R47") (pin "2") (pinfunction "2_2") (pintype "passive"))
    )
    (net (code "76") (name "Net-(IC4C-OUT)") (class "Default")
      (node (ref "C22") (pin "2") (pinfunction "2_2") (pintype "passive"))
      (node (ref "IC4") (pin "8") (pinfunction "OUT_8") (pintype "output"))
      (node (ref "R48") (pin "1") (pinfunction "1_1") (pintype "passive"))
    )
    (net (code "77") (name "Net-(IC4D--IN)") (class "Default")
      (node (ref "C24") (pin "1") (pinfunction "1_1") (pintype "passive"))
      (node (ref "IC4") (pin "13") (pinfunction "-IN_13") (pintype "input"))
      (node (ref "R51") (pin "1") (pinfunction "1_1") (pintype "passive"))
      (node (ref "R52") (pin "2") (pinfunction "2_2") (pintype "passive"))
    )
    (net (code "78") (name "Net-(IC4D-OUT)") (class "Default")
      (node (ref "C24") (pin "2") (pinfunction "2_2") (pintype "passive"))
      (node (ref "IC4") (pin "14") (pinfunction "OUT_14") (pintype "output"))
      (node (ref "R53") (pin "1") (pinfunction "1_1") (pintype "passive"))
    )
    (net (code "79") (name "Net-(IC5-ADC7)") (class "Default")
      (node (ref "IC5") (pin "22") (pinfunction "ADC7_22") (pintype "bidirectional"))
      (node (ref "RATE") (pin "P$2") (pinfunction "2_P$2") (pintype "passive"))
    )
    (net (code "80") (name "Net-(IC5-PB6(XTAL1{slash}TOSC1))") (class "Default")
      (node (ref "C1") (pin "1") (pinfunction "1_1") (pintype "passive"))
      (node (ref "IC5") (pin "7") (pinfunction "PB6(XTAL1/TOSC1)_7") (pintype "bidirectional"))
      (node (ref "Q1") (pin "2") (pinfunction "2_2") (pintype "passive"))
    )
    (net (code "81") (name "Net-(IC5-PB7(XTAL2{slash}TOSC2))") (class "Default")
      (node (ref "C2") (pin "1") (pinfunction "1_1") (pintype "passive"))
      (node (ref "IC5") (pin "8") (pinfunction "PB7(XTAL2/TOSC2)_8") (pintype "bidirectional"))
      (node (ref "Q1") (pin "1") (pinfunction "1_1") (pintype "passive"))
    )
    (net (code "82") (name "Net-(IC5-PD4(XCK{slash}T0))") (class "Default")
      (node (ref "IC5") (pin "2") (pinfunction "PD4(XCK/T0)_2") (pintype "bidirectional"))
      (node (ref "R55") (pin "2") (pinfunction "2_2") (pintype "passive"))
      (node (ref "SW1") (pin "1") (pinfunction "3_1") (pintype "bidirectional"))
      (node (ref "SW1") (pin "2") (pinfunction "1_2") (pintype "bidirectional"))
    )
    (net (code "83") (name "Net-(IC5-PD5(T1))") (class "Default")
      (node (ref "IC5") (pin "9") (pinfunction "PD5(T1)_9") (pintype "bidirectional"))
      (node (ref "SW1") (pin "A") (pinfunction "A_A") (pintype "passive"))
    )
    (net (code "84") (name "Net-(IC6-Y0)") (class "Default")
      (node (ref "FADER1") (pin "2") (pinfunction "2_2") (pintype "passive"))
      (node (ref "IC6") (pin "13") (pinfunction "Y0_13") (pintype "bidirectional"))
    )
    (net (code "85") (name "Net-(IC6-Y1)") (class "Default")
      (node (ref "FADER2") (pin "2") (pinfunction "2_2") (pintype "passive"))
      (node (ref "IC6") (pin "14") (pinfunction "Y1_14") (pintype "bidirectional"))
    )
    (net (code "86") (name "Net-(IC6-Y2)") (class "Default")
      (node (ref "FADER3") (pin "2") (pinfunction "2_2") (pintype "passive"))
      (node (ref "IC6") (pin "15") (pinfunction "Y2_15") (pintype "bidirectional"))
    )
    (net (code "87") (name "Net-(IC6-Y3)") (class "Default")
      (node (ref "FADER4") (pin "2") (pinfunction "2_2") (pintype "passive"))
      (node (ref "IC6") (pin "12") (pinfunction "Y3_12") (pintype "bidirectional"))
    )
    (net (code "88") (name "Net-(IC6-Y4)") (class "Default")
      (node (ref "FADER5") (pin "2") (pinfunction "2_2") (pintype "passive"))
      (node (ref "IC6") (pin "1") (pinfunction "Y4_1") (pintype "bidirectional"))
    )
    (net (code "89") (name "Net-(IC6-Y5)") (class "Default")
      (node (ref "FADER6") (pin "2") (pinfunction "2_2") (pintype "passive"))
      (node (ref "IC6") (pin "5") (pinfunction "Y5_5") (pintype "bidirectional"))
    )
    (net (code "90") (name "Net-(IC6-Y6)") (class "Default")
      (node (ref "FADER7") (pin "2") (pinfunction "2_2") (pintype "passive"))
      (node (ref "IC6") (pin "2") (pinfunction "Y6_2") (pintype "bidirectional"))
    )
    (net (code "91") (name "Net-(IC6-Y7)") (class "Default")
      (node (ref "FADER8") (pin "2") (pinfunction "2_2") (pintype "passive"))
      (node (ref "IC6") (pin "4") (pinfunction "Y7_4") (pintype "bidirectional"))
    )
    (net (code "92") (name "Net-(IC6-Z)") (class "Default")
      (node (ref "IC6") (pin "3") (pinfunction "Z_3") (pintype "bidirectional"))
      (node (ref "R60") (pin "2") (pinfunction "2_2") (pintype "passive"))
    )
    (net (code "93") (name "Net-(R9-Pad2)") (class "Default")
      (node (ref "R9") (pin "2") (pinfunction "2_2") (pintype "passive"))
      (node (ref "RESET") (pin "TIP") (pinfunction "TIP_TIP") (pintype "passive"))
    )
    (net (code "94") (name "Net-(RANGE-P)") (class "Default")
      (node (ref "RANGE") (pin "2") (pinfunction "P_2") (pintype "passive"))
      (node (ref "TR1") (pin "2") (pinfunction "2_2") (pintype "passive"))
      (node (ref "TR1") (pin "3") (pinfunction "3_3") (pintype "passive"))
    )
    (net (code "95") (name "Net-(SW1B-C)") (class "Default")
      (node (ref "R56") (pin "2") (pinfunction "2_2") (pintype "passive"))
      (node (ref "SW1") (pin "K") (pinfunction "C_K") (pintype "passive"))
    )
    (net (code "96") (name "Net-(T1-B)") (class "Default")
      (node (ref "R6") (pin "1") (pinfunction "1_1") (pintype "passive"))
      (node (ref "R7") (pin "2") (pinfunction "2_2") (pintype "passive"))
      (node (ref "T1") (pin "1") (pinfunction "B_1") (pintype "passive"))
    )
    (net (code "97") (name "Net-(T2-B)") (class "Default")
      (node (ref "R10") (pin "2") (pinfunction "2_2") (pintype "passive"))
      (node (ref "R9") (pin "1") (pinfunction "1_1") (pintype "passive"))
      (node (ref "T2") (pin "1") (pinfunction "B_1") (pintype "passive"))
    )
    (net (code "98") (name "unconnected-(CLOCK_OUT-SWITCH-PadNORM)") (class "Default")
      (node (ref "CLOCK_OUT") (pin "NORM") (pinfunction "SWITCH_NORM") (pintype "passive"))
    )
    (net (code "99") (name "unconnected-(CV_OUT-SWITCH-PadNORM)") (class "Default")
      (node (ref "CV_OUT") (pin "NORM") (pinfunction "SWITCH_NORM") (pintype "passive"))
    )
    (net (code "100") (name "unconnected-(GATE1-SWITCH-PadNORM)") (class "Default")
      (node (ref "GATE1") (pin "NORM") (pinfunction "SWITCH_NORM") (pintype "passive"))
    )
    (net (code "101") (name "unconnected-(GATE2-SWITCH-PadNORM)") (class "Default")
      (node (ref "GATE2") (pin "NORM") (pinfunction "SWITCH_NORM") (pintype "passive"))
    )
    (net (code "102") (name "unconnected-(GATE3-SWITCH-PadNORM)") (class "Default")
      (node (ref "GATE3") (pin "NORM") (pinfunction "SWITCH_NORM") (pintype "passive"))
    )
    (net (code "103") (name "unconnected-(GATE4-SWITCH-PadNORM)") (class "Default")
      (node (ref "GATE4") (pin "NORM") (pinfunction "SWITCH_NORM") (pintype "passive"))
    )
    (net (code "104") (name "unconnected-(GATE5-SWITCH-PadNORM)") (class "Default")
      (node (ref "GATE5") (pin "NORM") (pinfunction "SWITCH_NORM") (pintype "passive"))
    )
    (net (code "105") (name "unconnected-(GATE6-SWITCH-PadNORM)") (class "Default")
      (node (ref "GATE6") (pin "NORM") (pinfunction "SWITCH_NORM") (pintype "passive"))
    )
    (net (code "106") (name "unconnected-(GATE7-SWITCH-PadNORM)") (class "Default")
      (node (ref "GATE7") (pin "NORM") (pinfunction "SWITCH_NORM") (pintype "passive"))
    )
    (net (code "107") (name "unconnected-(GATE8-SWITCH-PadNORM)") (class "Default")
      (node (ref "GATE8") (pin "NORM") (pinfunction "SWITCH_NORM") (pintype "passive"))
    )
    (net (code "108") (name "unconnected-(IC5-ADC6-Pad19)") (class "Default")
      (node (ref "IC5") (pin "19") (pinfunction "ADC6_19") (pintype "bidirectional"))
    )
    (net (code "109") (name "unconnected-(IC5-AREF-Pad20)") (class "Default")
      (node (ref "IC5") (pin "20") (pinfunction "AREF_20") (pintype "bidirectional"))
    )
    (net (code "110") (name "unconnected-(IC5-PD0(RXD)-Pad30)") (class "Default")
      (node (ref "IC5") (pin "30") (pinfunction "PD0(RXD)_30") (pintype "bidirectional"))
    )
    (net (code "111") (name "unconnected-(IC5-PD1(TXD)-Pad31)") (class "Default")
      (node (ref "IC5") (pin "31") (pinfunction "PD1(TXD)_31") (pintype "bidirectional"))
    )
    (net (code "112") (name "unconnected-(RANGE-O-Pad1)") (class "Default")
      (node (ref "RANGE") (pin "1") (pinfunction "O_1") (pintype "passive"))
    )
    (net (code "113") (name "unconnected-(RESET-SWITCH-PadNORM)") (class "Default")
      (node (ref "RESET") (pin "NORM") (pinfunction "SWITCH_NORM") (pintype "passive"))
    )
  )
)
